# RFM69W.net
KiCad netlist of a schematic drawn in EAGLE
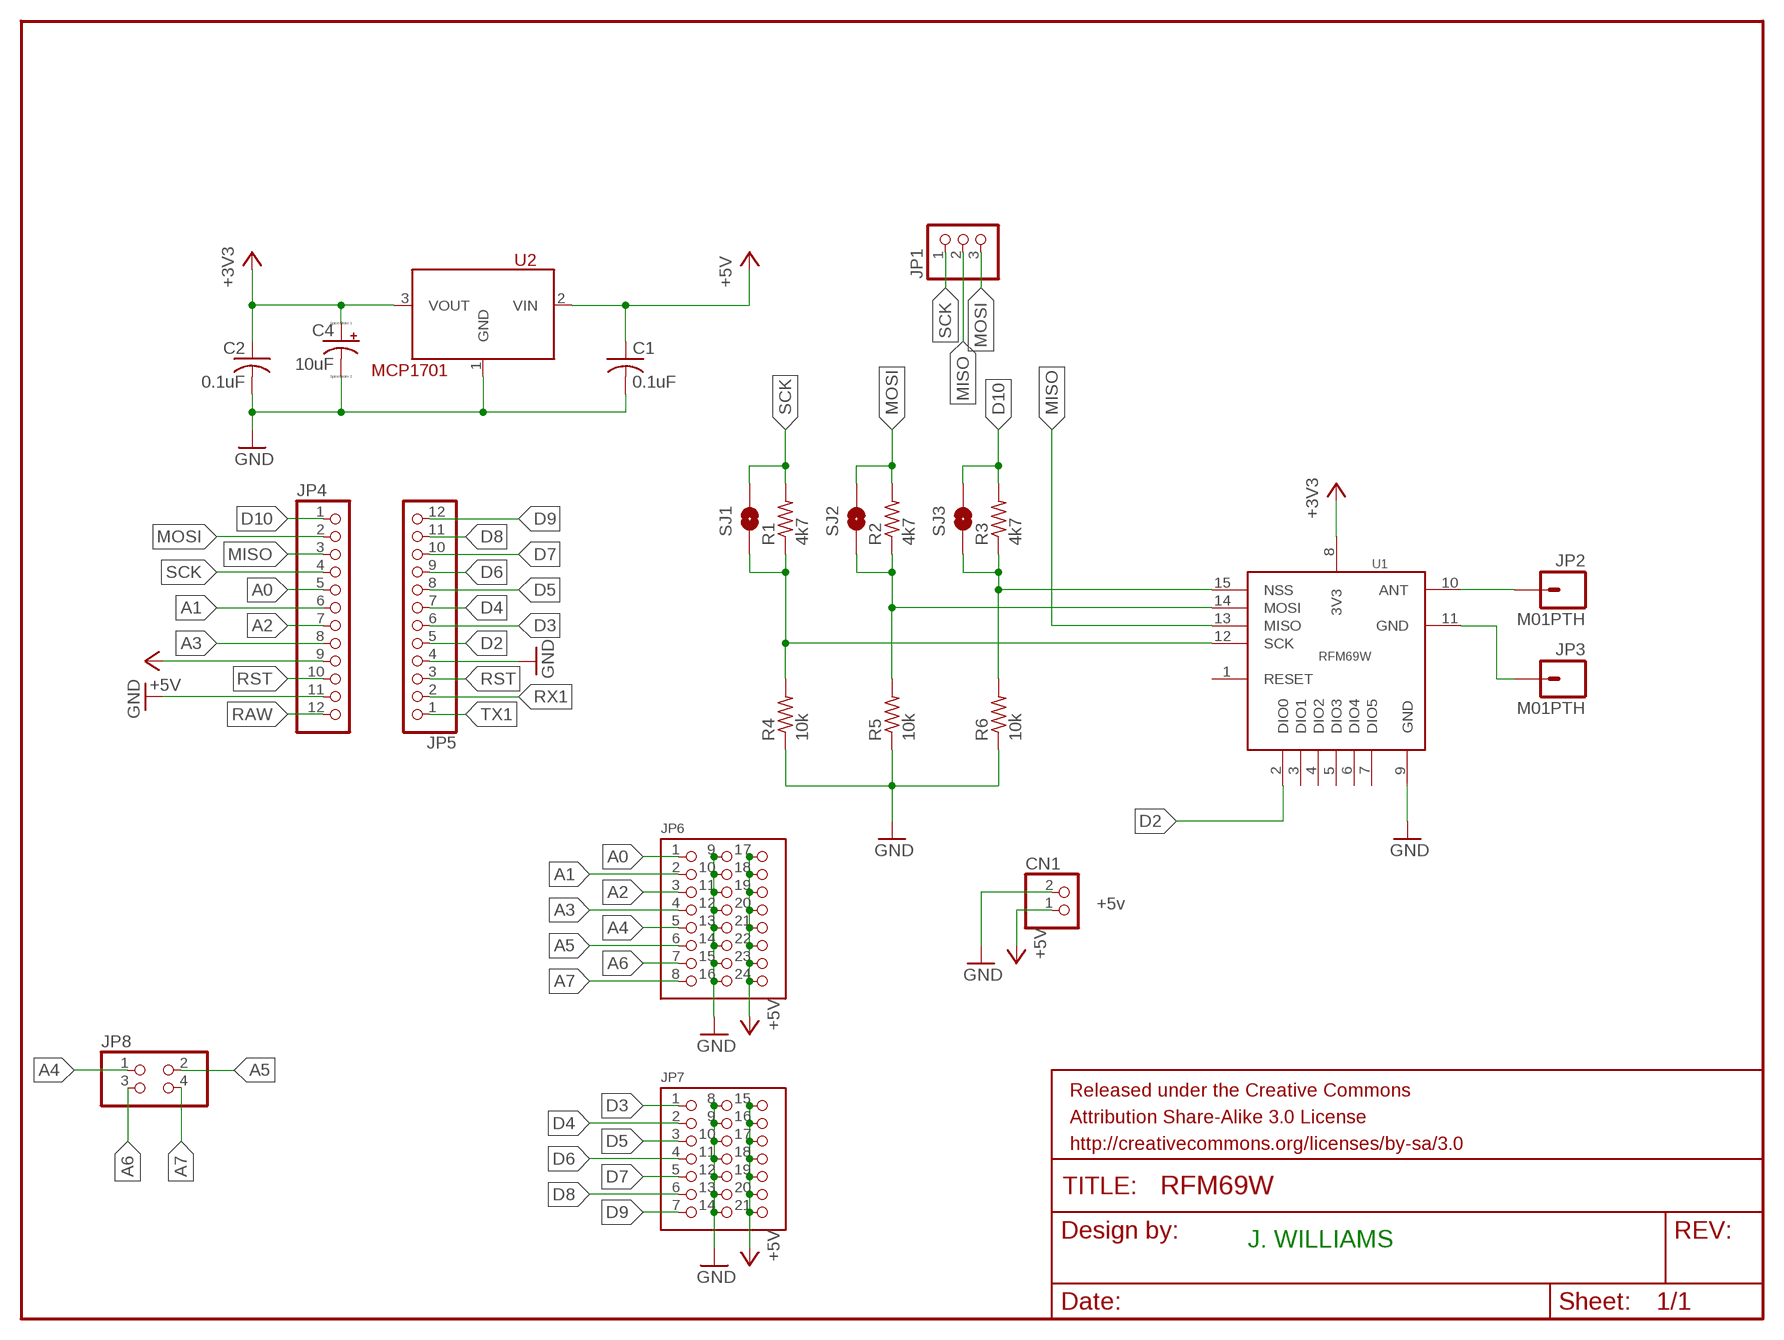
[diagram p0: schematic, sheet 1]

(export (version "E")
  (design (tool "Eeschema 10.0.6"))
  (components
    (comp (ref "C1")
      (value "0.1uF")
      (footprint "eagle-import:C1206")
      (libsource (lib "eagle-import") (part "C-USC1206"))
    )
    (comp (ref "C2")
      (value "0.1uF")
      (footprint "eagle-import:C1206")
      (libsource (lib "eagle-import") (part "C-USC1206"))
    )
    (comp (ref "C4")
      (value "10uF")
      (footprint "eagle-import:A_3216-18R")
      (libsource (lib "eagle-import") (part "CPOL-USA/3216-18R"))
    )
    (comp (ref "CN1")
      (value "+5v")
      (footprint "eagle-import:JST-PH-2-THM-RA")
      (libsource (lib "eagle-import") (part "JST_2PIN-THM-RA"))
    )
    (comp (ref "FRAME1")
      (value "FRAME-LETTER")
      (footprint "eagle-import:CREATIVE_COMMONS")
      (libsource (lib "eagle-import") (part "FRAME-LETTER"))
    )
    (comp (ref "JP1")
      (value "PINHD-1X3")
      (footprint "eagle-import:1X03")
      (libsource (lib "eagle-import") (part "PINHD-1X3"))
    )
    (comp (ref "JP2")
      (value "M01PTH")
      (footprint "eagle-import:1X01")
      (libsource (lib "eagle-import") (part "M01PTH"))
    )
    (comp (ref "JP3")
      (value "M01PTH")
      (footprint "eagle-import:1X01")
      (libsource (lib "eagle-import") (part "M01PTH"))
    )
    (comp (ref "JP4")
      (value "PINHD-1X12")
      (footprint "eagle-import:1X12")
      (libsource (lib "eagle-import") (part "PINHD-1X12"))
    )
    (comp (ref "JP5")
      (value "PINHD-1X12")
      (footprint "eagle-import:1X12")
      (libsource (lib "eagle-import") (part "PINHD-1X12"))
    )
    (comp (ref "JP6")
      (value "PIN_3X8")
      (footprint "eagle-import:PIN_3X8")
      (libsource (lib "eagle-import") (part "PIN_3X8"))
    )
    (comp (ref "JP7")
      (value "PIN_3X7")
      (footprint "eagle-import:PIN_3X7")
      (libsource (lib "eagle-import") (part "PIN_3X7"))
    )
    (comp (ref "JP8")
      (value "PINHD-2X2")
      (footprint "eagle-import:2X02")
      (libsource (lib "eagle-import") (part "PINHD-2X2"))
    )
    (comp (ref "R1")
      (value "4k7")
      (footprint "eagle-import:R1206")
      (libsource (lib "eagle-import") (part "R-US_R1206"))
    )
    (comp (ref "R2")
      (value "4k7")
      (footprint "eagle-import:R1206")
      (libsource (lib "eagle-import") (part "R-US_R1206"))
    )
    (comp (ref "R3")
      (value "4k7")
      (footprint "eagle-import:R1206")
      (libsource (lib "eagle-import") (part "R-US_R1206"))
    )
    (comp (ref "R4")
      (value "10k")
      (footprint "eagle-import:R1206")
      (libsource (lib "eagle-import") (part "R-US_R1206"))
    )
    (comp (ref "R5")
      (value "10k")
      (footprint "eagle-import:R1206")
      (libsource (lib "eagle-import") (part "R-US_R1206"))
    )
    (comp (ref "R6")
      (value "10k")
      (footprint "eagle-import:R1206")
      (libsource (lib "eagle-import") (part "R-US_R1206"))
    )
    (comp (ref "SJ1")
      (value "SOLDERJUMPERNO")
      (footprint "eagle-import:SJ_2S-NO")
      (libsource (lib "eagle-import") (part "SOLDERJUMPERNO"))
    )
    (comp (ref "SJ2")
      (value "SOLDERJUMPERNO")
      (footprint "eagle-import:SJ_2S-NO")
      (libsource (lib "eagle-import") (part "SOLDERJUMPERNO"))
    )
    (comp (ref "SJ3")
      (value "SOLDERJUMPERNO")
      (footprint "eagle-import:SJ_2S-NO")
      (libsource (lib "eagle-import") (part "SOLDERJUMPERNO"))
    )
    (comp (ref "U1")
      (value "RFM69W")
      (footprint "eagle-import:RFM69W")
      (libsource (lib "eagle-import") (part "RFM69W"))
    )
    (comp (ref "U2")
      (value "MCP1701")
      (footprint "eagle-import:SOT-89")
      (libsource (lib "eagle-import") (part "MCP1701"))
    )
  )
  (nets
    (net (code "1") (name "+3V3") (class "Default")
      (node (ref "C2") (pin "1") (pinfunction "1_1") (pintype "passive"))
      (node (ref "C4") (pin "+") (pinfunction "+_+") (pintype "passive"))
      (node (ref "U1") (pin "8") (pinfunction "3V3_8") (pintype "bidirectional"))
      (node (ref "U2") (pin "3") (pinfunction "VOUT_3") (pintype "bidirectional"))
    )
    (net (code "2") (name "+5V") (class "Default")
      (node (ref "C1") (pin "1") (pinfunction "1_1") (pintype "passive"))
      (node (ref "CN1") (pin "1") (pinfunction "2_1") (pintype "passive"))
      (node (ref "JP4") (pin "9") (pinfunction "9_9") (pintype "passive"))
      (node (ref "JP6") (pin "17") (pinfunction "17_17") (pintype "bidirectional"))
      (node (ref "JP6") (pin "18") (pinfunction "18_18") (pintype "bidirectional"))
      (node (ref "JP6") (pin "19") (pinfunction "19_19") (pintype "bidirectional"))
      (node (ref "JP6") (pin "20") (pinfunction "20_20") (pintype "bidirectional"))
      (node (ref "JP6") (pin "21") (pinfunction "21_21") (pintype "bidirectional"))
      (node (ref "JP6") (pin "22") (pinfunction "22_22") (pintype "bidirectional"))
      (node (ref "JP6") (pin "23") (pinfunction "23_23") (pintype "bidirectional"))
      (node (ref "JP6") (pin "24") (pinfunction "24_24") (pintype "bidirectional"))
      (node (ref "JP7") (pin "15") (pinfunction "15_15") (pintype "bidirectional"))
      (node (ref "JP7") (pin "16") (pinfunction "16_16") (pintype "bidirectional"))
      (node (ref "JP7") (pin "17") (pinfunction "17_17") (pintype "bidirectional"))
      (node (ref "JP7") (pin "18") (pinfunction "18_18") (pintype "bidirectional"))
      (node (ref "JP7") (pin "19") (pinfunction "19_19") (pintype "bidirectional"))
      (node (ref "JP7") (pin "20") (pinfunction "20_20") (pintype "bidirectional"))
      (node (ref "JP7") (pin "21") (pinfunction "21_21") (pintype "bidirectional"))
      (node (ref "U2") (pin "2") (pinfunction "VIN_2") (pintype "bidirectional"))
    )
    (net (code "3") (name "A0") (class "Default")
      (node (ref "JP4") (pin "5") (pinfunction "5_5") (pintype "passive"))
      (node (ref "JP6") (pin "1") (pinfunction "1_1") (pintype "bidirectional"))
    )
    (net (code "4") (name "A1") (class "Default")
      (node (ref "JP4") (pin "6") (pinfunction "6_6") (pintype "passive"))
      (node (ref "JP6") (pin "2") (pinfunction "2_2") (pintype "bidirectional"))
    )
    (net (code "5") (name "A2") (class "Default")
      (node (ref "JP4") (pin "7") (pinfunction "7_7") (pintype "passive"))
      (node (ref "JP6") (pin "3") (pinfunction "3_3") (pintype "bidirectional"))
    )
    (net (code "6") (name "A3") (class "Default")
      (node (ref "JP4") (pin "8") (pinfunction "8_8") (pintype "passive"))
      (node (ref "JP6") (pin "4") (pinfunction "4_4") (pintype "bidirectional"))
    )
    (net (code "7") (name "A4") (class "Default")
      (node (ref "JP6") (pin "5") (pinfunction "5_5") (pintype "bidirectional"))
      (node (ref "JP8") (pin "1") (pinfunction "1_1") (pintype "passive"))
    )
    (net (code "8") (name "A5") (class "Default")
      (node (ref "JP6") (pin "6") (pinfunction "6_6") (pintype "bidirectional"))
      (node (ref "JP8") (pin "2") (pinfunction "2_2") (pintype "passive"))
    )
    (net (code "9") (name "A6") (class "Default")
      (node (ref "JP6") (pin "7") (pinfunction "7_7") (pintype "bidirectional"))
      (node (ref "JP8") (pin "3") (pinfunction "3_3") (pintype "passive"))
    )
    (net (code "10") (name "A7") (class "Default")
      (node (ref "JP6") (pin "8") (pinfunction "8_8") (pintype "bidirectional"))
      (node (ref "JP8") (pin "4") (pinfunction "4_4") (pintype "passive"))
    )
    (net (code "11") (name "D2") (class "Default")
      (node (ref "JP5") (pin "5") (pinfunction "5_5") (pintype "passive"))
      (node (ref "U1") (pin "2") (pinfunction "DIO0_2") (pintype "bidirectional"))
    )
    (net (code "12") (name "D3") (class "Default")
      (node (ref "JP5") (pin "6") (pinfunction "6_6") (pintype "passive"))
      (node (ref "JP7") (pin "1") (pinfunction "1_1") (pintype "bidirectional"))
    )
    (net (code "13") (name "D4") (class "Default")
      (node (ref "JP5") (pin "7") (pinfunction "7_7") (pintype "passive"))
      (node (ref "JP7") (pin "2") (pinfunction "2_2") (pintype "bidirectional"))
    )
    (net (code "14") (name "D5") (class "Default")
      (node (ref "JP5") (pin "8") (pinfunction "8_8") (pintype "passive"))
      (node (ref "JP7") (pin "3") (pinfunction "3_3") (pintype "bidirectional"))
    )
    (net (code "15") (name "D6") (class "Default")
      (node (ref "JP5") (pin "9") (pinfunction "9_9") (pintype "passive"))
      (node (ref "JP7") (pin "4") (pinfunction "4_4") (pintype "bidirectional"))
    )
    (net (code "16") (name "D7") (class "Default")
      (node (ref "JP5") (pin "10") (pinfunction "10_10") (pintype "passive"))
      (node (ref "JP7") (pin "5") (pinfunction "5_5") (pintype "bidirectional"))
    )
    (net (code "17") (name "D8") (class "Default")
      (node (ref "JP5") (pin "11") (pinfunction "11_11") (pintype "passive"))
      (node (ref "JP7") (pin "6") (pinfunction "6_6") (pintype "bidirectional"))
    )
    (net (code "18") (name "D9") (class "Default")
      (node (ref "JP5") (pin "12") (pinfunction "12_12") (pintype "passive"))
      (node (ref "JP7") (pin "7") (pinfunction "7_7") (pintype "bidirectional"))
    )
    (net (code "19") (name "D10") (class "Default")
      (node (ref "JP4") (pin "1") (pinfunction "1_1") (pintype "passive"))
      (node (ref "R3") (pin "2") (pinfunction "2_2") (pintype "passive"))
      (node (ref "SJ3") (pin "2") (pinfunction "2_2") (pintype "passive"))
    )
    (net (code "20") (name "GND") (class "Default")
      (node (ref "C1") (pin "2") (pinfunction "2_2") (pintype "passive"))
      (node (ref "C2") (pin "2") (pinfunction "2_2") (pintype "passive"))
      (node (ref "C4") (pin "-") (pinfunction "-_-") (pintype "passive"))
      (node (ref "CN1") (pin "2") (pinfunction "1_2") (pintype "passive"))
      (node (ref "JP4") (pin "11") (pinfunction "11_11") (pintype "passive"))
      (node (ref "JP5") (pin "4") (pinfunction "4_4") (pintype "passive"))
      (node (ref "JP6") (pin "10") (pinfunction "10_10") (pintype "bidirectional"))
      (node (ref "JP6") (pin "11") (pinfunction "11_11") (pintype "bidirectional"))
      (node (ref "JP6") (pin "12") (pinfunction "12_12") (pintype "bidirectional"))
      (node (ref "JP6") (pin "13") (pinfunction "13_13") (pintype "bidirectional"))
      (node (ref "JP6") (pin "14") (pinfunction "14_14") (pintype "bidirectional"))
      (node (ref "JP6") (pin "15") (pinfunction "15_15") (pintype "bidirectional"))
      (node (ref "JP6") (pin "16") (pinfunction "16_16") (pintype "bidirectional"))
      (node (ref "JP6") (pin "9") (pinfunction "9_9") (pintype "bidirectional"))
      (node (ref "JP7") (pin "10") (pinfunction "10_10") (pintype "bidirectional"))
      (node (ref "JP7") (pin "11") (pinfunction "11_11") (pintype "bidirectional"))
      (node (ref "JP7") (pin "12") (pinfunction "12_12") (pintype "bidirectional"))
      (node (ref "JP7") (pin "13") (pinfunction "13_13") (pintype "bidirectional"))
      (node (ref "JP7") (pin "14") (pinfunction "14_14") (pintype "bidirectional"))
      (node (ref "JP7") (pin "8") (pinfunction "8_8") (pintype "bidirectional"))
      (node (ref "JP7") (pin "9") (pinfunction "9_9") (pintype "bidirectional"))
      (node (ref "R4") (pin "1") (pinfunction "1_1") (pintype "passive"))
      (node (ref "R5") (pin "1") (pinfunction "1_1") (pintype "passive"))
      (node (ref "R6") (pin "1") (pinfunction "1_1") (pintype "passive"))
      (node (ref "U1") (pin "9") (pinfunction "GND_9") (pintype "bidirectional"))
      (node (ref "U2") (pin "1") (pinfunction "GND_1") (pintype "bidirectional"))
    )
    (net (code "21") (name "MISO") (class "Default")
      (node (ref "JP1") (pin "2") (pinfunction "2_2") (pintype "passive"))
      (node (ref "JP4") (pin "3") (pinfunction "3_3") (pintype "passive"))
      (node (ref "U1") (pin "13") (pinfunction "MISO_13") (pintype "bidirectional"))
    )
    (net (code "22") (name "MOSI") (class "Default")
      (node (ref "JP1") (pin "3") (pinfunction "3_3") (pintype "passive"))
      (node (ref "JP4") (pin "2") (pinfunction "2_2") (pintype "passive"))
      (node (ref "R2") (pin "2") (pinfunction "2_2") (pintype "passive"))
      (node (ref "SJ2") (pin "2") (pinfunction "2_2") (pintype "passive"))
    )
    (net (code "23") (name "Net-(JP3-Pad1)") (class "Default")
      (node (ref "JP3") (pin "1") (pinfunction "1_1") (pintype "passive"))
      (node (ref "U1") (pin "11") (pinfunction "GND_11") (pintype "bidirectional"))
    )
    (net (code "24") (name "Net-(U1-ANT)") (class "Default")
      (node (ref "JP2") (pin "1") (pinfunction "1_1") (pintype "passive"))
      (node (ref "U1") (pin "10") (pinfunction "ANT_10") (pintype "bidirectional"))
    )
    (net (code "25") (name "Net-(U1-MOSI)") (class "Default")
      (node (ref "R2") (pin "1") (pinfunction "1_1") (pintype "passive"))
      (node (ref "R5") (pin "2") (pinfunction "2_2") (pintype "passive"))
      (node (ref "SJ2") (pin "1") (pinfunction "1_1") (pintype "passive"))
      (node (ref "U1") (pin "14") (pinfunction "MOSI_14") (pintype "bidirectional"))
    )
    (net (code "26") (name "Net-(U1-NSS)") (class "Default")
      (node (ref "R3") (pin "1") (pinfunction "1_1") (pintype "passive"))
      (node (ref "R6") (pin "2") (pinfunction "2_2") (pintype "passive"))
      (node (ref "SJ3") (pin "1") (pinfunction "1_1") (pintype "passive"))
      (node (ref "U1") (pin "15") (pinfunction "NSS_15") (pintype "bidirectional"))
    )
    (net (code "27") (name "Net-(U1-SCK)") (class "Default")
      (node (ref "R1") (pin "1") (pinfunction "1_1") (pintype "passive"))
      (node (ref "R4") (pin "2") (pinfunction "2_2") (pintype "passive"))
      (node (ref "SJ1") (pin "1") (pinfunction "1_1") (pintype "passive"))
      (node (ref "U1") (pin "12") (pinfunction "SCK_12") (pintype "bidirectional"))
    )
    (net (code "28") (name "RAW") (class "Default")
      (node (ref "JP4") (pin "12") (pinfunction "12_12") (pintype "passive"))
    )
    (net (code "29") (name "RST") (class "Default")
      (node (ref "JP4") (pin "10") (pinfunction "10_10") (pintype "passive"))
      (node (ref "JP5") (pin "3") (pinfunction "3_3") (pintype "passive"))
    )
    (net (code "30") (name "RX1") (class "Default")
      (node (ref "JP5") (pin "2") (pinfunction "2_2") (pintype "passive"))
    )
    (net (code "31") (name "SCK") (class "Default")
      (node (ref "JP1") (pin "1") (pinfunction "1_1") (pintype "passive"))
      (node (ref "JP4") (pin "4") (pinfunction "4_4") (pintype "passive"))
      (node (ref "R1") (pin "2") (pinfunction "2_2") (pintype "passive"))
      (node (ref "SJ1") (pin "2") (pinfunction "2_2") (pintype "passive"))
    )
    (net (code "32") (name "TX1") (class "Default")
      (node (ref "JP5") (pin "1") (pinfunction "1_1") (pintype "passive"))
    )
    (net (code "33") (name "unconnected-(U1-DIO1-Pad3)") (class "Default")
      (node (ref "U1") (pin "3") (pinfunction "DIO1_3") (pintype "bidirectional"))
    )
    (net (code "34") (name "unconnected-(U1-DIO2-Pad4)") (class "Default")
      (node (ref "U1") (pin "4") (pinfunction "DIO2_4") (pintype "bidirectional"))
    )
    (net (code "35") (name "unconnected-(U1-DIO3-Pad5)") (class "Default")
      (node (ref "U1") (pin "5") (pinfunction "DIO3_5") (pintype "bidirectional"))
    )
    (net (code "36") (name "unconnected-(U1-DIO4-Pad6)") (class "Default")
      (node (ref "U1") (pin "6") (pinfunction "DIO4_6") (pintype "bidirectional"))
    )
    (net (code "37") (name "unconnected-(U1-DIO5-Pad7)") (class "Default")
      (node (ref "U1") (pin "7") (pinfunction "DIO5_7") (pintype "bidirectional"))
    )
    (net (code "38") (name "unconnected-(U1-RESET-Pad1)") (class "Default")
      (node (ref "U1") (pin "1") (pinfunction "RESET_1") (pintype "bidirectional"))
    )
  )
)
